# Wi-Fi.net
KiCad netlist of a schematic drawn in Altium Designer
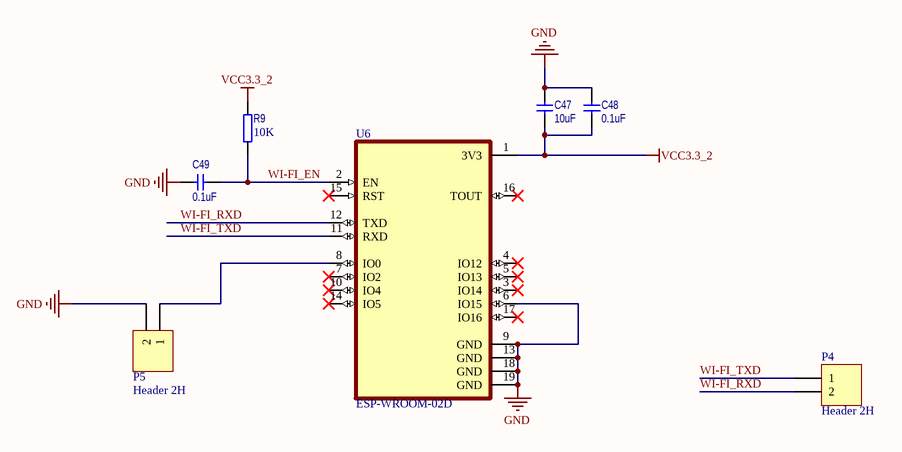
[diagram p0: Wi-Fi.SchDoc]

(export (version "E")
  (design (tool "Eeschema 10.0.6"))
  (components
    (comp (ref "C47")
      (value "10uF")
      (footprint "C 0603_M")
      (libsource (lib "baseboard") (part "ProE.tmp_22p_13"))
    )
    (comp (ref "C48")
      (value "0.1uF")
      (footprint "C 0603_M")
      (libsource (lib "baseboard") (part "ProE.tmp_22p_13"))
    )
    (comp (ref "C49")
      (value "0.1uF")
      (footprint "C 0603_M")
      (libsource (lib "baseboard") (part "ProE.tmp_22p_13"))
    )
    (comp (ref "P4")
      (value "Header 2H")
      (footprint "HDR2.54-LI-2P")
      (description "Header, 2-Pin, Right Angle")
      (fields (field (name "PUBLISHER") "Altium Limited"))
      (libsource (lib "baseboard") (part "Header 2H"))
    )
    (comp (ref "P5")
      (value "Header 2H")
      (footprint "HDR2.54-LI-2P")
      (description "Header, 2-Pin, Right Angle")
      (fields (field (name "PUBLISHER") "Altium Limited"))
      (libsource (lib "") (part "Header 2H_1"))
    )
    (comp (ref "R9") (value "10K") (footprint "0603R") (libsource (lib "baseboard") (part "ProE.tmp_10k_66")))
    (comp (ref "U6")
      (value "ESP-WROOM-02D")
      (footprint "ESP-WROOM-02D")
      (description "WiFi 802.11b/g/n Transceiver Module 2.4GHz ~ 2.5GHz Integrated, Trace Surface Mount")
      (fields (field (name "MF") "Espressif Systems"))
      (libsource (lib "Wi-Fi") (part "ESP-WROOM-02D"))
    )
  )
  (nets
    (net (code "1") (name "/WI-FI_EN") (class "Default")
      (node (ref "C49") (pin "1") (pintype "passive"))
      (node (ref "R9") (pin "1") (pintype "passive"))
      (node (ref "U6") (pin "2") (pinfunction "EN_2") (pintype "input"))
    )
    (net (code "2") (name "/WI-FI_RXD") (class "Default")
      (node (ref "P4") (pin "2") (pinfunction "2_2") (pintype "passive"))
      (node (ref "U6") (pin "12") (pinfunction "TXD_12") (pintype "bidirectional"))
    )
    (net (code "3") (name "/WI-FI_TXD") (class "Default")
      (node (ref "P4") (pin "1") (pinfunction "1_1") (pintype "passive"))
      (node (ref "U6") (pin "11") (pinfunction "RXD_11") (pintype "bidirectional"))
    )
    (net (code "4") (name "GND") (class "Default")
      (node (ref "C47") (pin "2") (pintype "passive"))
      (node (ref "C48") (pin "2") (pintype "passive"))
      (node (ref "C49") (pin "2") (pintype "passive"))
      (node (ref "P5") (pin "2") (pinfunction "2_2") (pintype "passive"))
      (node (ref "U6") (pin "13") (pinfunction "GND_13") (pintype "power_in"))
      (node (ref "U6") (pin "18") (pinfunction "GND_18") (pintype "power_in"))
      (node (ref "U6") (pin "19") (pinfunction "GND_19") (pintype "power_in"))
      (node (ref "U6") (pin "6") (pinfunction "IO15_6") (pintype "bidirectional"))
      (node (ref "U6") (pin "9") (pinfunction "GND_9") (pintype "power_in"))
    )
    (net (code "5") (name "Net-(U6-IO0)") (class "Default")
      (node (ref "P5") (pin "1") (pinfunction "1_1") (pintype "passive"))
      (node (ref "U6") (pin "8") (pinfunction "IO0_8") (pintype "bidirectional"))
    )
    (net (code "6") (name "VCC3.3_2") (class "Default")
      (node (ref "C47") (pin "1") (pintype "passive"))
      (node (ref "C48") (pin "1") (pintype "passive"))
      (node (ref "R9") (pin "2") (pintype "passive"))
      (node (ref "U6") (pin "1") (pinfunction "3V3_1") (pintype "power_in"))
    )
    (net (code "7") (name "unconnected-(U6-IO2-Pad7)") (class "Default")
      (node (ref "U6") (pin "7") (pinfunction "IO2_7") (pintype "bidirectional+no_connect"))
    )
    (net (code "8") (name "unconnected-(U6-IO4-Pad10)") (class "Default")
      (node (ref "U6") (pin "10") (pinfunction "IO4_10") (pintype "bidirectional+no_connect"))
    )
    (net (code "9") (name "unconnected-(U6-IO5-Pad14)") (class "Default")
      (node (ref "U6") (pin "14") (pinfunction "IO5_14") (pintype "bidirectional+no_connect"))
    )
    (net (code "10") (name "unconnected-(U6-IO12-Pad4)") (class "Default")
      (node (ref "U6") (pin "4") (pinfunction "IO12_4") (pintype "bidirectional+no_connect"))
    )
    (net (code "11") (name "unconnected-(U6-IO13-Pad5)") (class "Default")
      (node (ref "U6") (pin "5") (pinfunction "IO13_5") (pintype "bidirectional+no_connect"))
    )
    (net (code "12") (name "unconnected-(U6-IO14-Pad3)") (class "Default")
      (node (ref "U6") (pin "3") (pinfunction "IO14_3") (pintype "bidirectional+no_connect"))
    )
    (net (code "13") (name "unconnected-(U6-IO16-Pad17)") (class "Default")
      (node (ref "U6") (pin "17") (pinfunction "IO16_17") (pintype "bidirectional+no_connect"))
    )
    (net (code "14") (name "unconnected-(U6-RST-Pad15)") (class "Default")
      (node (ref "U6") (pin "15") (pinfunction "RST_15") (pintype "input+no_connect"))
    )
    (net (code "15") (name "unconnected-(U6-TOUT-Pad16)") (class "Default")
      (node (ref "U6") (pin "16") (pinfunction "TOUT_16") (pintype "bidirectional+no_connect"))
    )
  )
)
